# simulator.net
KiCad netlist of a schematic drawn in Altium Designer
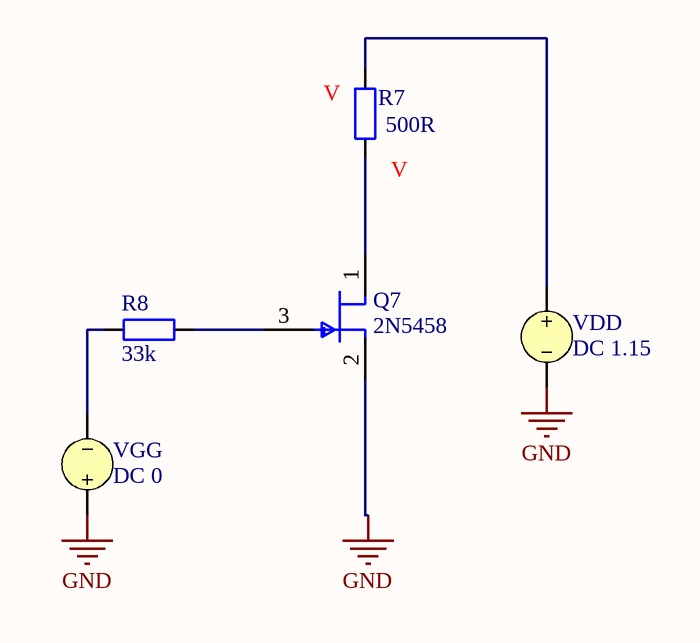
[diagram p0: simulator.SchDoc]

(export (version "E")
  (design (tool "Eeschema 10.0.6"))
  (components
    (comp (ref "Q7")
      (value "2N5458")
      (footprint "FP-29-11-MFG")
      (libsource (lib "Altium Content Vault") (part "2fe1325ee7984bd9864bb4197617735"))
    )
    (comp (ref "R7")
      (value "500R")
      (footprint "Resistor")
      (description "0.25W,Axial")
      (libsource (lib "CEF") (part "Resistor 0.25W 5mm"))
    )
    (comp (ref "R8")
      (value "33k")
      (footprint "Resistor")
      (description "0.25W,Axial")
      (libsource (lib "CEF") (part "Resistor 0.25W 5mm"))
    )
    (comp (ref "VDD")
      (value "DC 1.15")
      (description "Voltage Source")
      (fields (field (name "PUBLISHER") "Altium Limited"))
      (libsource (lib "Simulation Generic Components") (part "VSRC"))
    )
    (comp (ref "VGG")
      (value "DC 0")
      (description "Voltage Source")
      (fields (field (name "PUBLISHER") "Altium Limited"))
      (libsource (lib "Simulation Generic Components") (part "VSRC"))
    )
  )
  (nets
    (net (code "1") (name "GND") (class "Default")
      (node (ref "Q7") (pin "2") (pinfunction "SOURCE_2") (pintype "passive"))
      (node (ref "VDD") (pin "2") (pinfunction "2_2") (pintype "passive"))
      (node (ref "VGG") (pin "1") (pinfunction "1_1") (pintype "passive"))
    )
    (net (code "2") (name "Net-(Q7-DRAIN)") (class "Default")
      (node (ref "Q7") (pin "1") (pinfunction "DRAIN_1") (pintype "passive"))
      (node (ref "R7") (pin "1") (pinfunction "1_1") (pintype "passive"))
    )
    (net (code "3") (name "Net-(Q7-GATE)") (class "Default")
      (node (ref "Q7") (pin "3") (pinfunction "GATE_3") (pintype "passive"))
      (node (ref "R8") (pin "2") (pinfunction "2_2") (pintype "passive"))
    )
    (net (code "4") (name "Net-(R7-Pad2)") (class "Default")
      (node (ref "R7") (pin "2") (pinfunction "2_2") (pintype "passive"))
      (node (ref "VDD") (pin "1") (pinfunction "1_1") (pintype "passive"))
    )
    (net (code "5") (name "Net-(R8-Pad1)") (class "Default")
      (node (ref "R8") (pin "1") (pinfunction "1_1") (pintype "passive"))
      (node (ref "VGG") (pin "2") (pinfunction "2_2") (pintype "passive"))
    )
  )
)
